# FLYBACK_SWITCHING_POWER_SUPPLY_V1_0.net
KiCad netlist of a schematic drawn in Altium Designer
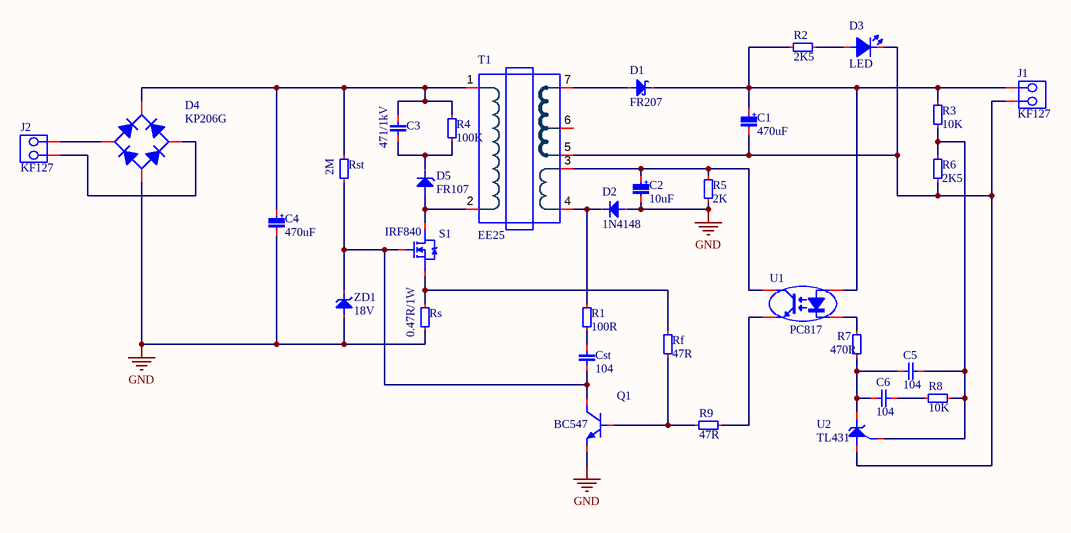
[diagram p0: FLYBACK_SWITCHING_POWER_SUPPLY_V1_0.SchDoc]

(export (version "E")
  (design (tool "Eeschema 10.0.6"))
  (components
    (comp (ref "C1")
      (value "470uF")
      (footprint "CAP_RAD_D10x12.5")
      (libsource (lib "MyAltiumLibrary") (part "Capacitor(Radian)"))
    )
    (comp (ref "C2")
      (value "10uF")
      (footprint "CAP_RAD_D05x11")
      (libsource (lib "MyAltiumLibrary") (part "Capacitor(Radian)"))
    )
    (comp (ref "C3")
      (value "471/1kV")
      (footprint "CAP_Ceramic_5MM")
      (libsource (lib "") (part "Capacitors(Disc)_1"))
    )
    (comp (ref "C4")
      (value "470uF")
      (footprint "CAP_RAD_D10x12.5")
      (libsource (lib "MyAltiumLibrary") (part "Capacitor(Radian)"))
    )
    (comp (ref "C5")
      (value "104")
      (footprint "CAP_Ceramic_2.5MM")
      (libsource (lib "MyAltiumLibrary") (part "Capacitors(Disc)"))
    )
    (comp (ref "C6")
      (value "104")
      (footprint "CAP_Ceramic_2.5MM")
      (libsource (lib "MyAltiumLibrary") (part "Capacitors(Disc)"))
    )
    (comp (ref "Cst")
      (value "104")
      (footprint "CAP_Ceramic_2.5MM")
      (libsource (lib "") (part "Capacitors(Disc)_1"))
    )
    (comp (ref "D1")
      (value "FR207")
      (footprint "DO-204AC-BK")
      (libsource (lib "MyAltiumLibrary") (part "Diode-FR207"))
    )
    (comp (ref "D2")
      (value "1N4148")
      (footprint "DO-204AH-RD")
      (libsource (lib "MyAltiumLibrary") (part "Diode-1N4148"))
    )
    (comp (ref "D3") (value "LED") (footprint "LED_5MM") (libsource (lib "MyAltiumLibrary") (part "LED 5MM")))
    (comp (ref "D4")
      (value "KP206G")
      (footprint "DIODE_2A")
      (libsource (lib "MyAltiumLibrary") (part "Diode_KP206G"))
    )
    (comp (ref "D5")
      (value "FR107")
      (footprint "DO-204AL-BK")
      (description "1A 1000V")
      (libsource (lib "MyAltiumLibrary") (part "Diode-FR107"))
    )
    (comp (ref "J1")
      (value "KF127")
      (footprint "DG127-5.0-02P-14-00AH")
      (libsource (lib "MyAltiumLibrary") (part "DG127-5.0-02P-14-00AH"))
    )
    (comp (ref "J2")
      (value "KF127")
      (footprint "DG127-5.0-02P-14-00AH")
      (libsource (lib "") (part "DG127-5.0-02P-14-00AH_1"))
    )
    (comp (ref "Q1")
      (value "BC547")
      (footprint "TO-92")
      (description "VCEO: 45 Vdc\r\nVCBO: 50 Vdc\r\nVEBO: 6.0 Vdc")
      (libsource (lib "MyAltiumLibrary") (part "Transistor-BC547"))
    )
    (comp (ref "R1")
      (value "100R")
      (footprint "RES-0.25W-H")
      (libsource (lib "MyAltiumLibrary") (part "Resistors THD"))
    )
    (comp (ref "R2") (value "2K5") (footprint "RES-0.25W-H") (libsource (lib "") (part "Resistors THD_2")))
    (comp (ref "R3")
      (value "10K")
      (footprint "RES-0.25W-H")
      (libsource (lib "MyAltiumLibrary") (part "Resistors THD"))
    )
    (comp (ref "R4")
      (value "100K")
      (footprint "RES-0.5W-H")
      (libsource (lib "MyAltiumLibrary") (part "Resistors THD"))
    )
    (comp (ref "R5")
      (value "2K")
      (footprint "RES-0.25W-H")
      (libsource (lib "MyAltiumLibrary") (part "Resistors THD"))
    )
    (comp (ref "R6")
      (value "2K5")
      (footprint "RES-0.25W-H")
      (libsource (lib "MyAltiumLibrary") (part "Resistors THD"))
    )
    (comp (ref "R7")
      (value "470R")
      (footprint "RES-0.25W-H")
      (libsource (lib "MyAltiumLibrary") (part "Resistors THD"))
    )
    (comp (ref "R8") (value "10K") (footprint "RES-0.25W-H") (libsource (lib "") (part "Resistors THD_1")))
    (comp (ref "R9") (value "47R") (footprint "RES-0.25W-V") (libsource (lib "") (part "Resistors THD_1")))
    (comp (ref "Rf")
      (value "47R")
      (footprint "RES-0.25W-H")
      (libsource (lib "MyAltiumLibrary") (part "Resistors THD"))
    )
    (comp (ref "Rs")
      (value "0.47R/1W")
      (footprint "RES-1W-H")
      (libsource (lib "MyAltiumLibrary") (part "Resistors THD"))
    )
    (comp (ref "Rst")
      (value "2M")
      (footprint "RES-0.25W-H")
      (libsource (lib "MyAltiumLibrary") (part "Resistors THD"))
    )
    (comp (ref "S1")
      (value "IRF840")
      (footprint "TO-220-HEAT-SINK-1")
      (libsource (lib "MyAltiumLibrary") (part "Mosfet-IRF840"))
    )
    (comp (ref "T1")
      (value "EE25")
      (footprint "TRANSFORMER-FLUOLAMP-8W")
      (libsource (lib "MyAltiumLibrary") (part "TRANS-FLUOLAMP-V0"))
    )
    (comp (ref "U1")
      (value "PC817")
      (footprint "PC817-DIP")
      (libsource (lib "MyAltiumLibrary") (part "Opto-PC817"))
    )
    (comp (ref "U2")
      (value "TL431")
      (footprint "TO-92")
      (libsource (lib "MyAltiumLibrary") (part "Ic-TL431"))
    )
    (comp (ref "ZD1")
      (value "18V")
      (footprint "DO-204AL-RD")
      (libsource (lib "MyAltiumLibrary") (part "Diode-Zener"))
    )
  )
  (nets
    (net (code "1") (name "GND") (class "Default")
      (node (ref "C2") (pin "2") (pinfunction "2_2") (pintype "passive"))
      (node (ref "C4") (pin "2") (pinfunction "2_2") (pintype "passive"))
      (node (ref "D2") (pin "1") (pinfunction "1_1") (pintype "passive"))
      (node (ref "D4") (pin "1") (pinfunction "1_1") (pintype "passive"))
      (node (ref "Q1") (pin "3") (pinfunction "E_3") (pintype "passive"))
      (node (ref "R5") (pin "1") (pinfunction "1_1") (pintype "passive"))
      (node (ref "Rs") (pin "1") (pinfunction "1_1") (pintype "passive"))
      (node (ref "ZD1") (pin "1") (pinfunction "1_1") (pintype "passive"))
    )
    (net (code "2") (name "Net-(C3-Pad1)") (class "Default")
      (node (ref "C3") (pin "1") (pinfunction "1_1") (pintype "passive"))
      (node (ref "D5") (pin "2") (pinfunction "2_2") (pintype "passive"))
      (node (ref "R4") (pin "1") (pinfunction "1_1") (pintype "passive"))
    )
    (net (code "3") (name "Net-(C3-Pad2)") (class "Default")
      (node (ref "C3") (pin "2") (pinfunction "2_2") (pintype "passive"))
      (node (ref "C4") (pin "1") (pinfunction "1_1") (pintype "passive"))
      (node (ref "D4") (pin "4") (pinfunction "4_4") (pintype "passive"))
      (node (ref "R4") (pin "2") (pinfunction "2_2") (pintype "passive"))
      (node (ref "Rst") (pin "2") (pinfunction "2_2") (pintype "passive"))
      (node (ref "T1") (pin "1") (pinfunction "1_1") (pintype "passive"))
    )
    (net (code "4") (name "Net-(C5-Pad1)") (class "Default")
      (node (ref "C5") (pin "1") (pinfunction "1_1") (pintype "passive"))
      (node (ref "R3") (pin "1") (pinfunction "1_1") (pintype "passive"))
      (node (ref "R6") (pin "2") (pinfunction "2_2") (pintype "passive"))
      (node (ref "R8") (pin "1") (pinfunction "1_1") (pintype "passive"))
      (node (ref "U2") (pin "1") (pinfunction "1_1") (pintype "passive"))
    )
    (net (code "5") (name "Net-(C5-Pad2)") (class "Default")
      (node (ref "C5") (pin "2") (pinfunction "2_2") (pintype "passive"))
      (node (ref "C6") (pin "2") (pinfunction "2_2") (pintype "passive"))
      (node (ref "R7") (pin "1") (pinfunction "1_1") (pintype "passive"))
      (node (ref "U2") (pin "3") (pinfunction "3_3") (pintype "passive"))
    )
    (net (code "6") (name "Net-(C6-Pad1)") (class "Default")
      (node (ref "C6") (pin "1") (pinfunction "1_1") (pintype "passive"))
      (node (ref "R8") (pin "2") (pinfunction "2_2") (pintype "passive"))
    )
    (net (code "7") (name "Net-(Cst-Pad2)") (class "Default")
      (node (ref "Cst") (pin "2") (pinfunction "2_2") (pintype "passive"))
      (node (ref "R1") (pin "1") (pinfunction "1_1") (pintype "passive"))
    )
    (net (code "8") (name "Net-(D1-Pad1)") (class "Default")
      (node (ref "D1") (pin "1") (pinfunction "1_1") (pintype "passive"))
      (node (ref "T1") (pin "7") (pinfunction "7_7") (pintype "passive"))
    )
    (net (code "9") (name "Net-(D2-Pad2)") (class "Default")
      (node (ref "D2") (pin "2") (pinfunction "2_2") (pintype "passive"))
      (node (ref "R1") (pin "2") (pinfunction "2_2") (pintype "passive"))
      (node (ref "T1") (pin "4") (pinfunction "4_4") (pintype "passive"))
    )
    (net (code "10") (name "Net-(D3-A)") (class "Default")
      (node (ref "D3") (pin "1") (pinfunction "A_1") (pintype "passive"))
      (node (ref "R2") (pin "2") (pinfunction "2_2") (pintype "passive"))
    )
    (net (code "11") (name "Net-(D3-K)") (class "Default")
      (node (ref "C1") (pin "2") (pinfunction "2_2") (pintype "passive"))
      (node (ref "D3") (pin "2") (pinfunction "K_2") (pintype "passive"))
      (node (ref "J1") (pin "1") (pinfunction "1_1") (pintype "passive"))
      (node (ref "R6") (pin "1") (pinfunction "1_1") (pintype "passive"))
      (node (ref "T1") (pin "5") (pinfunction "5_5") (pintype "passive"))
      (node (ref "U2") (pin "2") (pinfunction "2_2") (pintype "passive"))
    )
    (net (code "12") (name "Net-(D4-Pad2)") (class "Default")
      (node (ref "D4") (pin "2") (pinfunction "2_2") (pintype "passive"))
      (node (ref "J2") (pin "1") (pinfunction "1_1") (pintype "passive"))
    )
    (net (code "13") (name "Net-(D4-Pad3)") (class "Default")
      (node (ref "D4") (pin "3") (pinfunction "3_3") (pintype "passive"))
      (node (ref "J2") (pin "2") (pinfunction "2_2") (pintype "passive"))
    )
    (net (code "14") (name "Net-(Q1-B)") (class "Default")
      (node (ref "Q1") (pin "2") (pinfunction "B_2") (pintype "passive"))
      (node (ref "R9") (pin "2") (pinfunction "2_2") (pintype "passive"))
      (node (ref "Rf") (pin "1") (pinfunction "1_1") (pintype "passive"))
    )
    (net (code "15") (name "Net-(Q1-C)") (class "Default")
      (node (ref "Cst") (pin "1") (pinfunction "1_1") (pintype "passive"))
      (node (ref "Q1") (pin "1") (pinfunction "C_1") (pintype "passive"))
      (node (ref "Rst") (pin "1") (pinfunction "1_1") (pintype "passive"))
      (node (ref "S1") (pin "1") (pinfunction "G_1") (pintype "passive"))
      (node (ref "ZD1") (pin "2") (pinfunction "2_2") (pintype "passive"))
    )
    (net (code "16") (name "Net-(S1-D)") (class "Default")
      (node (ref "D5") (pin "1") (pinfunction "1_1") (pintype "passive"))
      (node (ref "S1") (pin "2") (pinfunction "D_2") (pintype "passive"))
      (node (ref "T1") (pin "2") (pinfunction "2_2") (pintype "passive"))
    )
    (net (code "17") (name "Net-(S1-S)") (class "Default")
      (node (ref "Rf") (pin "2") (pinfunction "2_2") (pintype "passive"))
      (node (ref "Rs") (pin "2") (pinfunction "2_2") (pintype "passive"))
      (node (ref "S1") (pin "3") (pinfunction "S_3") (pintype "passive"))
    )
    (net (code "18") (name "Net-(U1-A)") (class "Default")
      (node (ref "C1") (pin "1") (pinfunction "1_1") (pintype "passive"))
      (node (ref "D1") (pin "2") (pinfunction "2_2") (pintype "passive"))
      (node (ref "J1") (pin "2") (pinfunction "2_2") (pintype "passive"))
      (node (ref "R2") (pin "1") (pinfunction "1_1") (pintype "passive"))
      (node (ref "R3") (pin "2") (pinfunction "2_2") (pintype "passive"))
      (node (ref "U1") (pin "1") (pinfunction "A_1") (pintype "passive"))
    )
    (net (code "19") (name "Net-(U1-C)") (class "Default")
      (node (ref "C2") (pin "1") (pinfunction "1_1") (pintype "passive"))
      (node (ref "R5") (pin "2") (pinfunction "2_2") (pintype "passive"))
      (node (ref "T1") (pin "3") (pinfunction "3_3") (pintype "passive"))
      (node (ref "U1") (pin "4") (pinfunction "C_4") (pintype "passive"))
    )
    (net (code "20") (name "Net-(U1-E)") (class "Default")
      (node (ref "R9") (pin "1") (pinfunction "1_1") (pintype "passive"))
      (node (ref "U1") (pin "3") (pinfunction "E_3") (pintype "passive"))
    )
    (net (code "21") (name "Net-(U1-K)") (class "Default")
      (node (ref "R7") (pin "2") (pinfunction "2_2") (pintype "passive"))
      (node (ref "U1") (pin "2") (pinfunction "K_2") (pintype "passive"))
    )
    (net (code "22") (name "unconnected-(T1-Pad6)") (class "Default")
      (node (ref "T1") (pin "6") (pinfunction "6_6") (pintype "passive"))
    )
  )
)
